# RGB-Controller.net
KiCad netlist of a schematic drawn in EasyEDA
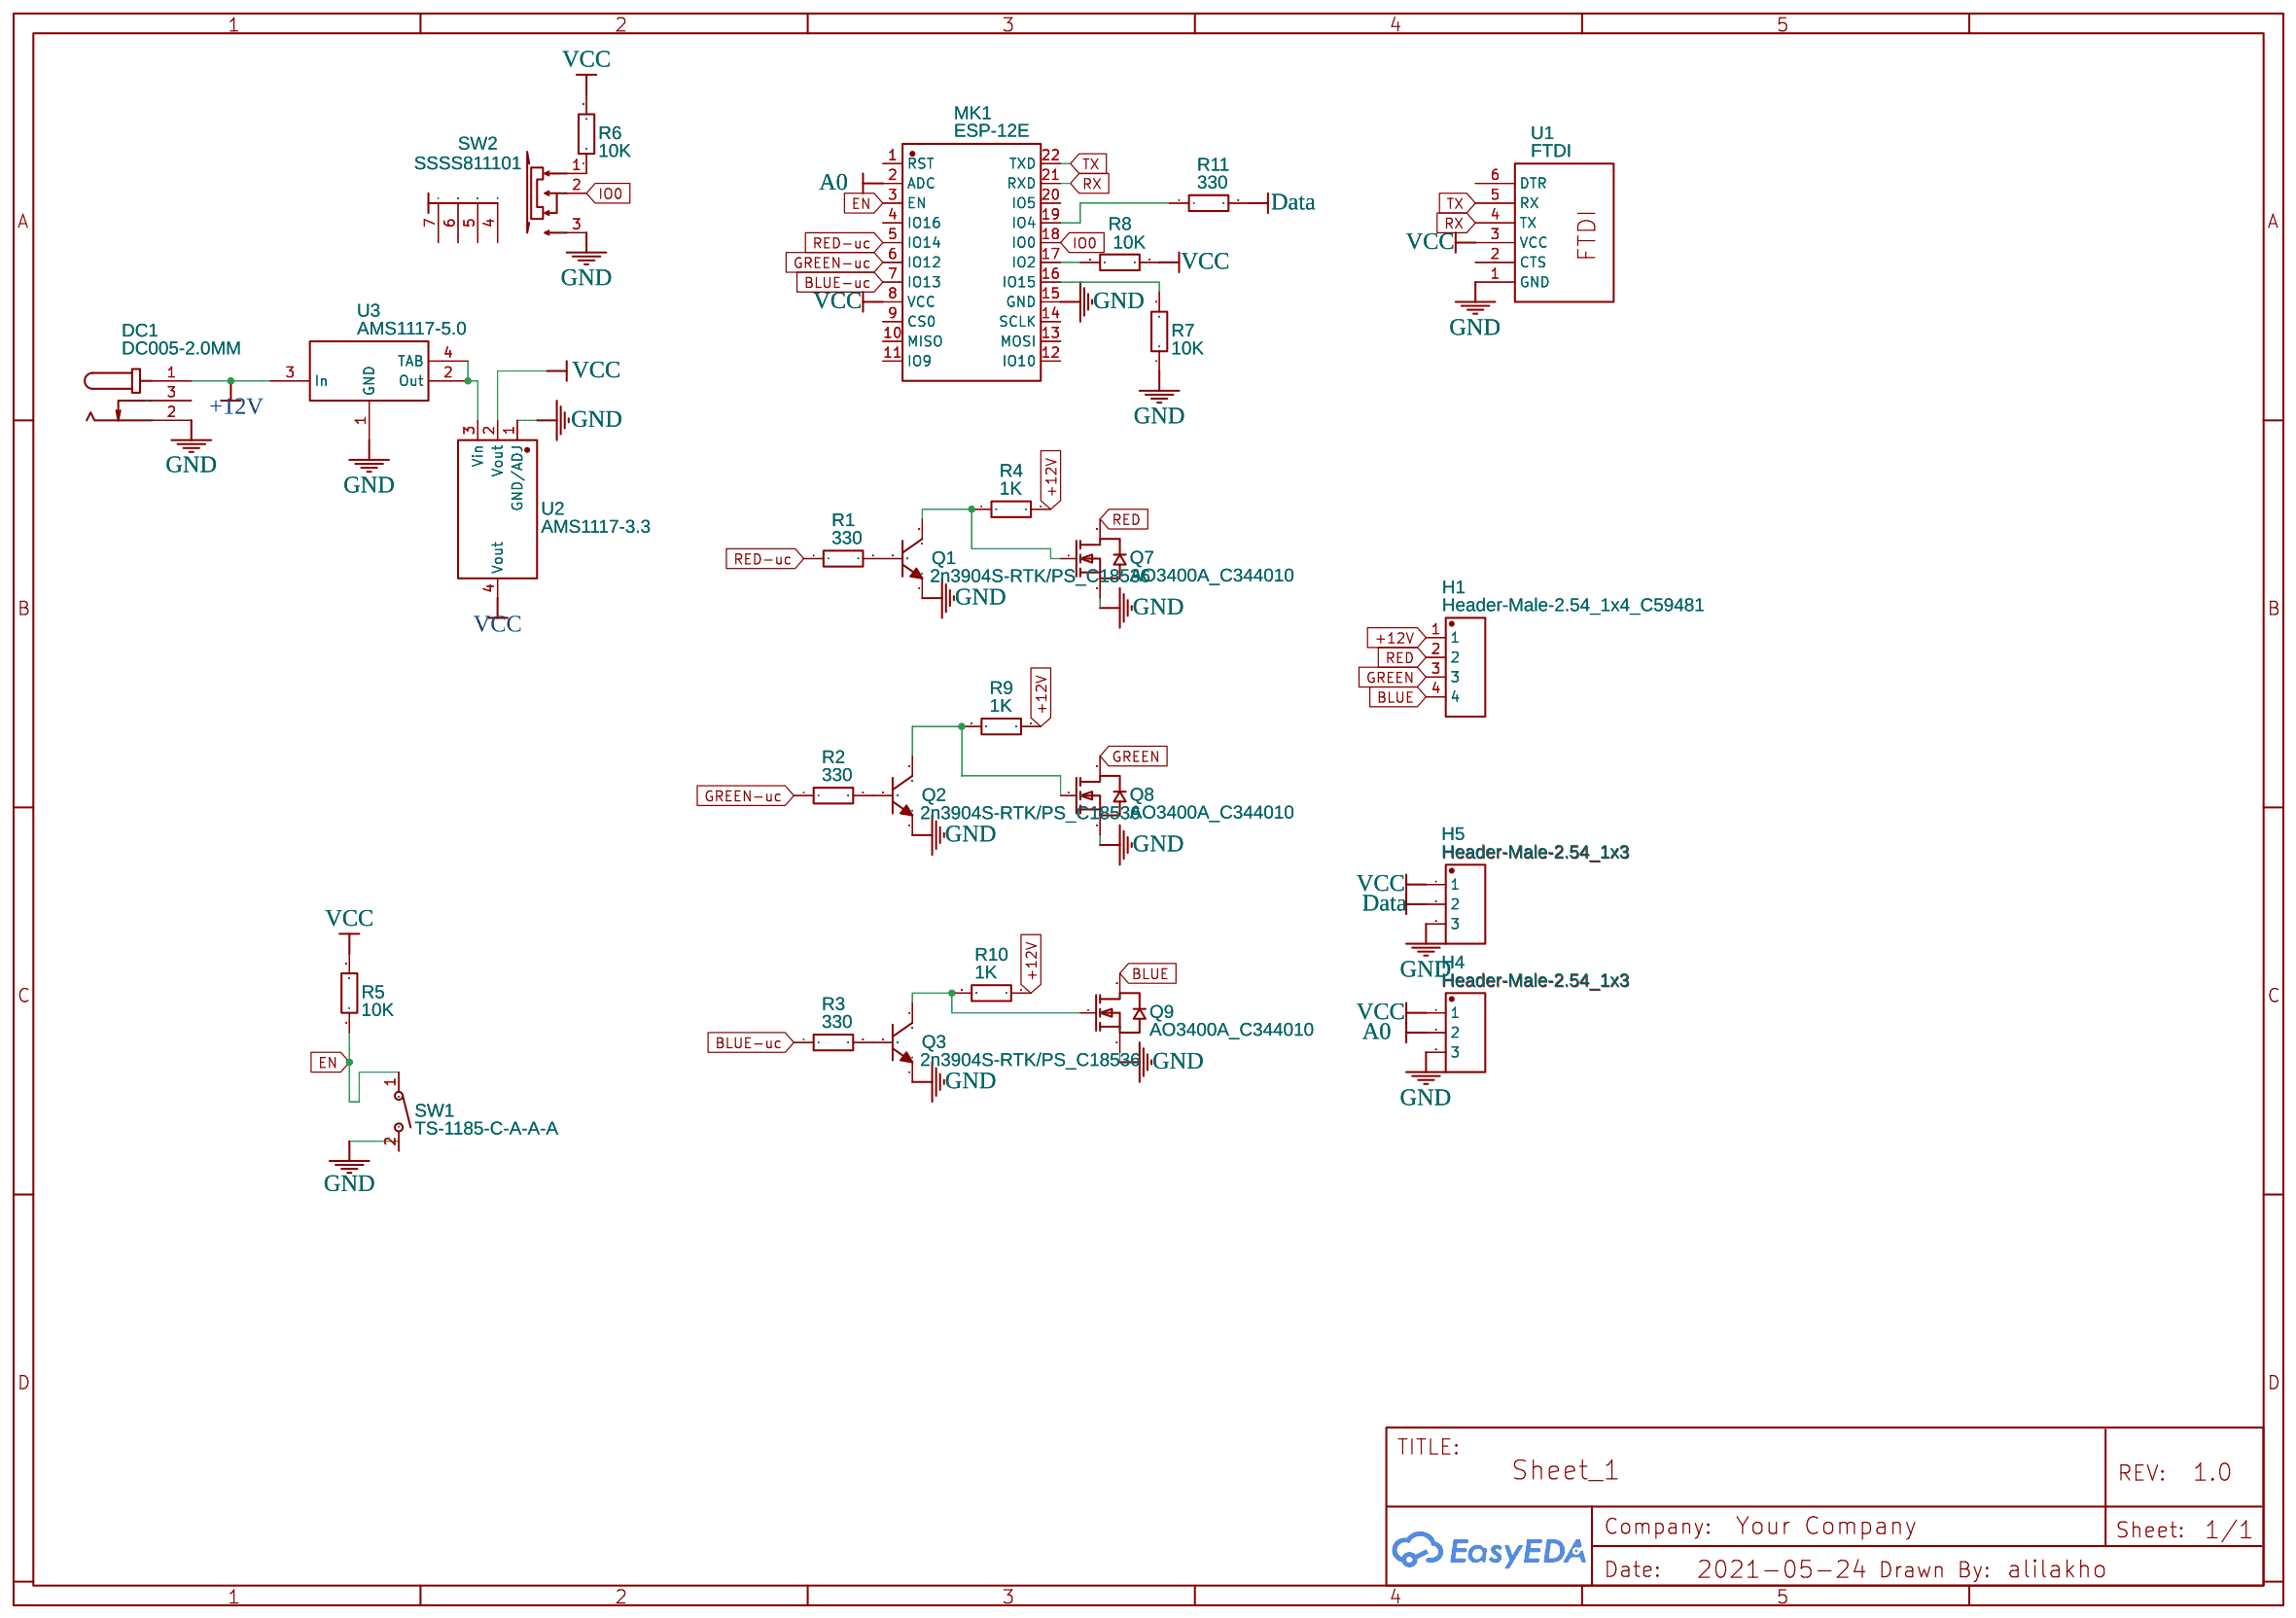
[diagram p0: schematic sheet]

(export (version "E")
  (design (tool "Eeschema 10.0.6"))
  (components
    (comp (ref "DC1")
      (value "DC005-2.0MM")
      (fields (field (name "BOM_Supplier Part") "C111567"))
      (libsource (lib "") (part "DC005-2.0MM"))
    )
    (comp (ref "H1")
      (value "Header-Male-2.54_1x4_C59481")
      (fields
        (field (name "BOM_Manufacturer Part") "Headers  Pins 1*4P")
        (field (name "BOM_Supplier Part") "C59481")
      )
      (libsource (lib "") (part "Header-Male-2.54_1x4_C59481"))
    )
    (comp (ref "H4") (value "Header-Male-2.54_1x3") (libsource (lib "") (part "Header-Male-2.54_1x3")))
    (comp (ref "H5") (value "Header-Male-2.54_1x3") (libsource (lib "") (part "Header-Male-2.54_1x3")))
    (comp (ref "MK1")
      (value "ESP-12E")
      (fields (field (name "BOM_Supplier Part") "C89297"))
      (libsource (lib "") (part "ESP-12E"))
    )
    (comp (ref "Q1")
      (value "2n3904S-RTK/PS_C18536")
      (fields
        (field (name "BOM_Manufacturer Part") "2n3904S-RTK/PS")
        (field (name "BOM_Supplier Part") "C18536")
      )
      (libsource (lib "") (part "2n3904S-RTK/PS_C18536"))
    )
    (comp (ref "Q2")
      (value "2n3904S-RTK/PS_C18536")
      (fields
        (field (name "BOM_Manufacturer Part") "2n3904S-RTK/PS")
        (field (name "BOM_Supplier Part") "C18536")
      )
      (libsource (lib "") (part "2n3904S-RTK/PS_C18536"))
    )
    (comp (ref "Q3")
      (value "2n3904S-RTK/PS_C18536")
      (fields
        (field (name "BOM_Manufacturer Part") "2n3904S-RTK/PS")
        (field (name "BOM_Supplier Part") "C18536")
      )
      (libsource (lib "") (part "2n3904S-RTK/PS_C18536"))
    )
    (comp (ref "Q7")
      (value "AO3400A_C344010")
      (fields (field (name "BOM_Manufacturer Part") "AO3400A") (field (name "BOM_Supplier Part") "C344010"))
      (libsource (lib "") (part "AO3400A_C344010"))
    )
    (comp (ref "Q8")
      (value "AO3400A_C344010")
      (fields (field (name "BOM_Manufacturer Part") "AO3400A") (field (name "BOM_Supplier Part") "C344010"))
      (libsource (lib "") (part "AO3400A_C344010"))
    )
    (comp (ref "Q9")
      (value "AO3400A_C344010")
      (fields (field (name "BOM_Manufacturer Part") "AO3400A") (field (name "BOM_Supplier Part") "C344010"))
      (libsource (lib "") (part "AO3400A_C344010"))
    )
    (comp (ref "R1")
      (value "330")
      (fields
        (field (name "BOM_Manufacturer Part") "0805W8J0331T5E")
        (field (name "BOM_Supplier Part") "C25306")
      )
      (libsource (lib "") (part "0805W8J0331T5E"))
    )
    (comp (ref "R2")
      (value "330")
      (fields
        (field (name "BOM_Manufacturer Part") "0805W8J0331T5E")
        (field (name "BOM_Supplier Part") "C25306")
      )
      (libsource (lib "") (part "0805W8J0331T5E"))
    )
    (comp (ref "R3")
      (value "330")
      (fields
        (field (name "BOM_Manufacturer Part") "0805W8J0331T5E")
        (field (name "BOM_Supplier Part") "C25306")
      )
      (libsource (lib "") (part "0805W8J0331T5E"))
    )
    (comp (ref "R4")
      (value "1K")
      (fields
        (field (name "BOM_Manufacturer Part") "1210W3J0102T5E")
        (field (name "BOM_Supplier Part") "C25681")
      )
      (libsource (lib "") (part "1210W3J0102T5E"))
    )
    (comp (ref "R5")
      (value "10K")
      (fields
        (field (name "BOM_Manufacturer Part") "1206W4F1002T5E")
        (field (name "BOM_Supplier Part") "C17902")
      )
      (libsource (lib "") (part "1206W4F1002T5E"))
    )
    (comp (ref "R6")
      (value "10K")
      (fields
        (field (name "BOM_Manufacturer Part") "1206W4F1002T5E")
        (field (name "BOM_Supplier Part") "C17902")
      )
      (libsource (lib "") (part "1206W4F1002T5E"))
    )
    (comp (ref "R7")
      (value "10K")
      (fields
        (field (name "BOM_Manufacturer Part") "1206W4F1002T5E")
        (field (name "BOM_Supplier Part") "C17902")
      )
      (libsource (lib "") (part "1206W4F1002T5E"))
    )
    (comp (ref "R8")
      (value "10K")
      (fields
        (field (name "BOM_Manufacturer Part") "1206W4F1002T5E")
        (field (name "BOM_Supplier Part") "C17902")
      )
      (libsource (lib "") (part "1206W4F1002T5E_1"))
    )
    (comp (ref "R9")
      (value "1K")
      (fields
        (field (name "BOM_Manufacturer Part") "1210W3J0102T5E")
        (field (name "BOM_Supplier Part") "C25681")
      )
      (libsource (lib "") (part "1210W3J0102T5E"))
    )
    (comp (ref "R10")
      (value "1K")
      (fields
        (field (name "BOM_Manufacturer Part") "1210W3J0102T5E")
        (field (name "BOM_Supplier Part") "C25681")
      )
      (libsource (lib "") (part "1210W3J0102T5E"))
    )
    (comp (ref "R11")
      (value "330")
      (fields
        (field (name "BOM_Manufacturer Part") "0805W8J0331T5E")
        (field (name "BOM_Supplier Part") "C25306")
      )
      (libsource (lib "") (part "0805W8J0331T5E"))
    )
    (comp (ref "SW1")
      (value "TS-1185-C-A-A-A")
      (fields (field (name "BOM_Supplier Part") "C561518"))
      (libsource (lib "") (part "TS-1185-C-A-A-A"))
    )
    (comp (ref "SW2")
      (value "SSSS811101")
      (fields (field (name "BOM_Supplier Part") "C109335"))
      (libsource (lib "") (part "SSSS811101"))
    )
    (comp (ref "U1") (value "FTDI") (libsource (lib "") (part "FTDI")))
    (comp (ref "U2")
      (value "AMS1117-3.3")
      (fields (field (name "BOM_Supplier Part") "C6186"))
      (libsource (lib "") (part "AMS1117-3.3"))
    )
    (comp (ref "U3")
      (value "AMS1117-5.0")
      (fields (field (name "BOM_Supplier Part") "C6187"))
      (libsource (lib "") (part "AMS1117-5.0"))
    )
  )
  (nets
    (net (code "1") (name "+12V") (class "Default")
      (node (ref "DC1") (pin "1") (pinfunction "1_1") (pintype "unspecified"))
      (node (ref "H1") (pin "1") (pinfunction "1_1") (pintype "unspecified"))
      (node (ref "R10") (pin "1") (pinfunction "1_1") (pintype "input"))
      (node (ref "R4") (pin "1") (pinfunction "1_1") (pintype "input"))
      (node (ref "R9") (pin "1") (pinfunction "1_1") (pintype "input"))
      (node (ref "U3") (pin "3") (pinfunction "In_3") (pintype "unspecified"))
    )
    (net (code "2") (name "A0") (class "Default")
      (node (ref "H4") (pin "2") (pinfunction "2_2") (pintype "unspecified"))
      (node (ref "MK1") (pin "2") (pinfunction "ADC_2") (pintype "unspecified"))
    )
    (net (code "3") (name "BLUE") (class "Default")
      (node (ref "H1") (pin "4") (pinfunction "4_4") (pintype "unspecified"))
      (node (ref "Q9") (pin "3") (pinfunction "D_3") (pintype "unspecified"))
    )
    (net (code "4") (name "BLUE-uc") (class "Default")
      (node (ref "MK1") (pin "7") (pinfunction "IO13_7") (pintype "unspecified"))
      (node (ref "R3") (pin "1") (pinfunction "1_1") (pintype "input"))
    )
    (net (code "5") (name "Data") (class "Default")
      (node (ref "H5") (pin "2") (pinfunction "2_2") (pintype "unspecified"))
      (node (ref "R11") (pin "2") (pinfunction "2_2") (pintype "input"))
    )
    (net (code "6") (name "EN") (class "Default")
      (node (ref "MK1") (pin "3") (pinfunction "EN_3") (pintype "unspecified"))
      (node (ref "R5") (pin "1") (pinfunction "1_1") (pintype "input"))
      (node (ref "SW1") (pin "1") (pinfunction "1_1") (pintype "unspecified"))
    )
    (net (code "7") (name "GND") (class "Default")
      (node (ref "DC1") (pin "2") (pinfunction "2_2") (pintype "unspecified"))
      (node (ref "H4") (pin "3") (pinfunction "3_3") (pintype "unspecified"))
      (node (ref "H5") (pin "3") (pinfunction "3_3") (pintype "unspecified"))
      (node (ref "MK1") (pin "15") (pinfunction "GND_15") (pintype "unspecified"))
      (node (ref "Q1") (pin "1") (pinfunction "E_1") (pintype "input"))
      (node (ref "Q2") (pin "1") (pinfunction "E_1") (pintype "input"))
      (node (ref "Q3") (pin "1") (pinfunction "E_1") (pintype "input"))
      (node (ref "Q7") (pin "2") (pinfunction "S_2") (pintype "unspecified"))
      (node (ref "Q8") (pin "2") (pinfunction "S_2") (pintype "unspecified"))
      (node (ref "Q9") (pin "2") (pinfunction "S_2") (pintype "unspecified"))
      (node (ref "R7") (pin "1") (pinfunction "1_1") (pintype "input"))
      (node (ref "SW1") (pin "2") (pinfunction "2_2") (pintype "unspecified"))
      (node (ref "SW2") (pin "3") (pinfunction "3_3") (pintype "unspecified"))
      (node (ref "U1") (pin "1") (pinfunction "GND_1") (pintype "unspecified"))
      (node (ref "U2") (pin "1") (pinfunction "GND/ADJ_1") (pintype "unspecified"))
      (node (ref "U3") (pin "1") (pinfunction "GND_1") (pintype "unspecified"))
    )
    (net (code "8") (name "GREEN") (class "Default")
      (node (ref "H1") (pin "3") (pinfunction "3_3") (pintype "unspecified"))
      (node (ref "Q8") (pin "3") (pinfunction "D_3") (pintype "unspecified"))
    )
    (net (code "9") (name "GREEN-uc") (class "Default")
      (node (ref "MK1") (pin "6") (pinfunction "IO12_6") (pintype "unspecified"))
      (node (ref "R2") (pin "1") (pinfunction "1_1") (pintype "input"))
    )
    (net (code "10") (name "IO0") (class "Default")
      (node (ref "MK1") (pin "18") (pinfunction "IO0_18") (pintype "unspecified"))
      (node (ref "SW2") (pin "2") (pinfunction "2_2") (pintype "unspecified"))
    )
    (net (code "11") (name "Net-(MK1-IO2)") (class "Default")
      (node (ref "MK1") (pin "17") (pinfunction "IO2_17") (pintype "unspecified"))
      (node (ref "R8") (pin "2") (pinfunction "2_2") (pintype "input"))
    )
    (net (code "12") (name "Net-(MK1-IO4)") (class "Default")
      (node (ref "MK1") (pin "19") (pinfunction "IO4_19") (pintype "unspecified"))
      (node (ref "R11") (pin "1") (pinfunction "1_1") (pintype "input"))
    )
    (net (code "13") (name "Net-(MK1-IO15)") (class "Default")
      (node (ref "MK1") (pin "16") (pinfunction "IO15_16") (pintype "unspecified"))
      (node (ref "R7") (pin "2") (pinfunction "2_2") (pintype "input"))
    )
    (net (code "14") (name "Net-(Q1-B)") (class "Default")
      (node (ref "Q1") (pin "2") (pinfunction "B_2") (pintype "input"))
      (node (ref "R1") (pin "2") (pinfunction "2_2") (pintype "input"))
    )
    (net (code "15") (name "Net-(Q1-C)") (class "Default")
      (node (ref "Q1") (pin "3") (pinfunction "C_3") (pintype "input"))
      (node (ref "Q7") (pin "1") (pinfunction "G_1") (pintype "unspecified"))
      (node (ref "R4") (pin "2") (pinfunction "2_2") (pintype "input"))
    )
    (net (code "16") (name "Net-(Q2-B)") (class "Default")
      (node (ref "Q2") (pin "2") (pinfunction "B_2") (pintype "input"))
      (node (ref "R2") (pin "2") (pinfunction "2_2") (pintype "input"))
    )
    (net (code "17") (name "Net-(Q2-C)") (class "Default")
      (node (ref "Q2") (pin "3") (pinfunction "C_3") (pintype "input"))
      (node (ref "Q8") (pin "1") (pinfunction "G_1") (pintype "unspecified"))
      (node (ref "R9") (pin "2") (pinfunction "2_2") (pintype "input"))
    )
    (net (code "18") (name "Net-(Q3-B)") (class "Default")
      (node (ref "Q3") (pin "2") (pinfunction "B_2") (pintype "input"))
      (node (ref "R3") (pin "2") (pinfunction "2_2") (pintype "input"))
    )
    (net (code "19") (name "Net-(Q3-C)") (class "Default")
      (node (ref "Q3") (pin "3") (pinfunction "C_3") (pintype "input"))
      (node (ref "Q9") (pin "1") (pinfunction "G_1") (pintype "unspecified"))
      (node (ref "R10") (pin "2") (pinfunction "2_2") (pintype "input"))
    )
    (net (code "20") (name "Net-(R6-Pad1)") (class "Default")
      (node (ref "R6") (pin "1") (pinfunction "1_1") (pintype "input"))
      (node (ref "SW2") (pin "1") (pinfunction "1_1") (pintype "unspecified"))
    )
    (net (code "21") (name "Net-(U2-Vin)") (class "Default")
      (node (ref "U2") (pin "3") (pinfunction "Vin_3") (pintype "unspecified"))
      (node (ref "U3") (pin "2") (pinfunction "Out_2") (pintype "unspecified"))
      (node (ref "U3") (pin "4") (pinfunction "TAB_4") (pintype "unspecified"))
    )
    (net (code "22") (name "RED") (class "Default")
      (node (ref "H1") (pin "2") (pinfunction "2_2") (pintype "unspecified"))
      (node (ref "Q7") (pin "3") (pinfunction "D_3") (pintype "unspecified"))
    )
    (net (code "23") (name "RED-uc") (class "Default")
      (node (ref "MK1") (pin "5") (pinfunction "IO14_5") (pintype "unspecified"))
      (node (ref "R1") (pin "1") (pinfunction "1_1") (pintype "input"))
    )
    (net (code "24") (name "RX") (class "Default")
      (node (ref "MK1") (pin "21") (pinfunction "RXD_21") (pintype "unspecified"))
      (node (ref "U1") (pin "4") (pinfunction "TX_4") (pintype "unspecified"))
    )
    (net (code "25") (name "TX") (class "Default")
      (node (ref "MK1") (pin "22") (pinfunction "TXD_22") (pintype "unspecified"))
      (node (ref "U1") (pin "5") (pinfunction "RX_5") (pintype "unspecified"))
    )
    (net (code "26") (name "VCC") (class "Default")
      (node (ref "H4") (pin "1") (pinfunction "1_1") (pintype "unspecified"))
      (node (ref "H5") (pin "1") (pinfunction "1_1") (pintype "unspecified"))
      (node (ref "MK1") (pin "8") (pinfunction "VCC_8") (pintype "unspecified"))
      (node (ref "R5") (pin "2") (pinfunction "2_2") (pintype "input"))
      (node (ref "R6") (pin "2") (pinfunction "2_2") (pintype "input"))
      (node (ref "R8") (pin "1") (pinfunction "1_1") (pintype "input"))
      (node (ref "U1") (pin "3") (pinfunction "VCC_3") (pintype "unspecified"))
      (node (ref "U2") (pin "2") (pinfunction "Vout_2") (pintype "unspecified"))
      (node (ref "U2") (pin "4") (pinfunction "Vout_4") (pintype "unspecified"))
    )
    (net (code "27") (name "unconnected-(DC1-Pad3)") (class "Default")
      (node (ref "DC1") (pin "3") (pinfunction "3_3") (pintype "unspecified"))
    )
    (net (code "28") (name "unconnected-(MK1-CS0-Pad9)") (class "Default")
      (node (ref "MK1") (pin "9") (pinfunction "CS0_9") (pintype "unspecified"))
    )
    (net (code "29") (name "unconnected-(MK1-IO5-Pad20)") (class "Default")
      (node (ref "MK1") (pin "20") (pinfunction "IO5_20") (pintype "unspecified"))
    )
    (net (code "30") (name "unconnected-(MK1-IO9-Pad11)") (class "Default")
      (node (ref "MK1") (pin "11") (pinfunction "IO9_11") (pintype "unspecified"))
    )
    (net (code "31") (name "unconnected-(MK1-IO10-Pad12)") (class "Default")
      (node (ref "MK1") (pin "12") (pinfunction "IO10_12") (pintype "unspecified"))
    )
    (net (code "32") (name "unconnected-(MK1-IO16-Pad4)") (class "Default")
      (node (ref "MK1") (pin "4") (pinfunction "IO16_4") (pintype "unspecified"))
    )
    (net (code "33") (name "unconnected-(MK1-MISO-Pad10)") (class "Default")
      (node (ref "MK1") (pin "10") (pinfunction "MISO_10") (pintype "unspecified"))
    )
    (net (code "34") (name "unconnected-(MK1-MOSI-Pad13)") (class "Default")
      (node (ref "MK1") (pin "13") (pinfunction "MOSI_13") (pintype "unspecified"))
    )
    (net (code "35") (name "unconnected-(MK1-RST-Pad1)") (class "Default")
      (node (ref "MK1") (pin "1") (pinfunction "RST_1") (pintype "unspecified"))
    )
    (net (code "36") (name "unconnected-(MK1-SCLK-Pad14)") (class "Default")
      (node (ref "MK1") (pin "14") (pinfunction "SCLK_14") (pintype "unspecified"))
    )
    (net (code "37") (name "unconnected-(SW2-Pad4)") (class "Default")
      (node (ref "SW2") (pin "4") (pinfunction "4_4") (pintype "unspecified"))
    )
    (net (code "38") (name "unconnected-(SW2-Pad5)") (class "Default")
      (node (ref "SW2") (pin "5") (pinfunction "5_5") (pintype "unspecified"))
    )
    (net (code "39") (name "unconnected-(SW2-Pad6)") (class "Default")
      (node (ref "SW2") (pin "6") (pinfunction "6_6") (pintype "unspecified"))
    )
    (net (code "40") (name "unconnected-(SW2-Pad7)") (class "Default")
      (node (ref "SW2") (pin "7") (pinfunction "7_7") (pintype "unspecified"))
    )
    (net (code "41") (name "unconnected-(U1-CTS-Pad2)") (class "Default")
      (node (ref "U1") (pin "2") (pinfunction "CTS_2") (pintype "unspecified"))
    )
    (net (code "42") (name "unconnected-(U1-DTR-Pad6)") (class "Default")
      (node (ref "U1") (pin "6") (pinfunction "DTR_6") (pintype "unspecified"))
    )
  )
)
